# LIS3MDL.net
KiCad netlist of a schematic drawn in Altium Designer
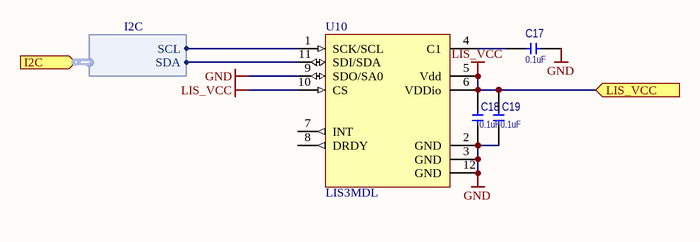
[diagram p0: LIS3MDL.SchDoc]

(export (version "E")
  (design (tool "Eeschema 10.0.6"))
  (components
    (comp (ref "C17")
      (value "0.1uF")
      (footprint "CERCAP 0402")
      (description "Capacitor")
      (fields (field (name "Comment") "CERCAP 0402 0.1uF * X7R"))
      (libsource (lib "!main") (part "!Capacitor"))
    )
    (comp (ref "C18")
      (value "0.1uF")
      (footprint "CERCAP 0402")
      (description "Capacitor")
      (fields (field (name "Comment") "CERCAP 0402 0.1uF * X7R"))
      (libsource (lib "!main") (part "!Capacitor"))
    )
    (comp (ref "C19")
      (value "0.1uF")
      (footprint "CERCAP 0402")
      (description "Capacitor")
      (fields (field (name "Comment") "CERCAP 0402 0.1uF * X7R"))
      (libsource (lib "!main") (part "!Capacitor"))
    )
    (comp (ref "U10")
      (value "LIS3MDL")
      (footprint "LGA12_LIS3MDL")
      (description "Mag")
      (libsource (lib "sensors") (part "LIS3MDL"))
    )
  )
  (nets
    (net (code "2") (name "/SCL") (class "Default")
      (node (ref "U10") (pin "1") (pinfunction "SCK/SCL_1") (pintype "input"))
    )
    (net (code "3") (name "/SDA") (class "Default")
      (node (ref "U10") (pin "11") (pinfunction "SDI/SDA_11") (pintype "bidirectional"))
    )
    (net (code "5") (name "GND") (class "Default")
      (node (ref "C17") (pin "1") (pintype "passive"))
      (node (ref "C18") (pin "1") (pintype "passive"))
      (node (ref "C19") (pin "1") (pintype "passive"))
      (node (ref "U10") (pin "12") (pinfunction "GND_12") (pintype "power_in"))
      (node (ref "U10") (pin "2") (pinfunction "GND_2") (pintype "power_in"))
      (node (ref "U10") (pin "3") (pinfunction "GND_3") (pintype "power_in"))
      (node (ref "U10") (pin "9") (pinfunction "SDO/SA0_9") (pintype "bidirectional"))
    )
    (net (code "6") (name "LIS_VCC") (class "Default")
      (node (ref "C18") (pin "2") (pintype "passive"))
      (node (ref "C19") (pin "2") (pintype "passive"))
      (node (ref "U10") (pin "10") (pinfunction "CS_10") (pintype "input"))
      (node (ref "U10") (pin "5") (pinfunction "Vdd_5") (pintype "power_in"))
      (node (ref "U10") (pin "6") (pinfunction "VDDio_6") (pintype "power_in"))
    )
    (net (code "7") (name "Net-(U10-C1)") (class "Default")
      (node (ref "C17") (pin "2") (pintype "passive"))
      (node (ref "U10") (pin "4") (pinfunction "C1_4") (pintype "passive"))
    )
    (net (code "8") (name "unconnected-(U10-DRDY-Pad8)") (class "Default")
      (node (ref "U10") (pin "8") (pinfunction "DRDY_8") (pintype "output"))
    )
    (net (code "9") (name "unconnected-(U10-INT-Pad7)") (class "Default")
      (node (ref "U10") (pin "7") (pinfunction "INT_7") (pintype "output"))
    )
  )
)
